# 08_MISC.net
KiCad netlist of a schematic drawn in Altium Designer
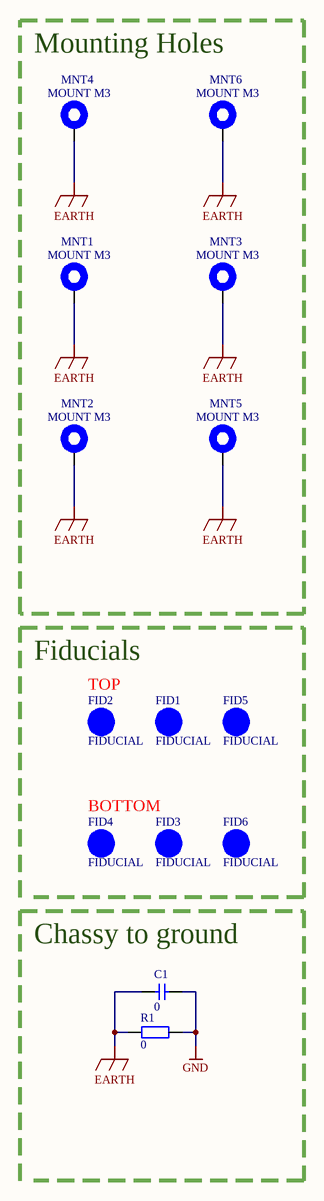
[diagram p0: 08 MISC.SchDoc]

(export (version "E")
  (design (tool "Eeschema 10.0.6"))
  (components
    (comp (ref "C1") (value "0") (footprint "CAPC2012X04N") (libsource (lib "altium_symbol") (part "TEMP_1")))
    (comp (ref "FID1")
      (value "FIDUCIAL")
      (footprint "FIDUCIAL")
      (libsource (lib "altium_symbol") (part "FIDUCIAL"))
    )
    (comp (ref "FID2")
      (value "FIDUCIAL")
      (footprint "FIDUCIAL")
      (libsource (lib "altium_symbol") (part "FIDUCIAL"))
    )
    (comp (ref "FID3")
      (value "FIDUCIAL")
      (footprint "FIDUCIAL")
      (libsource (lib "altium_symbol") (part "FIDUCIAL"))
    )
    (comp (ref "FID4")
      (value "FIDUCIAL")
      (footprint "FIDUCIAL")
      (libsource (lib "altium_symbol") (part "FIDUCIAL"))
    )
    (comp (ref "FID5")
      (value "FIDUCIAL")
      (footprint "FIDUCIAL")
      (libsource (lib "altium_symbol") (part "FIDUCIAL"))
    )
    (comp (ref "FID6")
      (value "FIDUCIAL")
      (footprint "FIDUCIAL")
      (libsource (lib "altium_symbol") (part "FIDUCIAL"))
    )
    (comp (ref "MNT1")
      (value "MOUNT M3")
      (footprint "MOUNT_M3")
      (libsource (lib "altium_symbol") (part "MOUNT_M3"))
    )
    (comp (ref "MNT2")
      (value "MOUNT M3")
      (footprint "MOUNT_M3")
      (libsource (lib "altium_symbol") (part "MOUNT_M3"))
    )
    (comp (ref "MNT3")
      (value "MOUNT M3")
      (footprint "MOUNT_M3")
      (libsource (lib "altium_symbol") (part "MOUNT_M3"))
    )
    (comp (ref "MNT4")
      (value "MOUNT M3")
      (footprint "MOUNT_M3")
      (libsource (lib "altium_symbol") (part "MOUNT_M3"))
    )
    (comp (ref "MNT5")
      (value "MOUNT M3")
      (footprint "MOUNT_M3")
      (libsource (lib "altium_symbol") (part "MOUNT_M3"))
    )
    (comp (ref "MNT6")
      (value "MOUNT M3")
      (footprint "MOUNT_M3")
      (libsource (lib "altium_symbol") (part "MOUNT_M3"))
    )
    (comp (ref "R1") (value "0") (footprint "RESC2012X04N") (libsource (lib "altium_symbol") (part "TEMP")))
  )
  (nets
    (net (code "1") (name "EARTH") (class "Default")
      (node (ref "C1") (pin "1") (pinfunction "1_1") (pintype "passive"))
      (node (ref "MNT1") (pin "1") (pinfunction "1_1") (pintype "passive"))
      (node (ref "MNT2") (pin "1") (pinfunction "1_1") (pintype "passive"))
      (node (ref "MNT3") (pin "1") (pinfunction "1_1") (pintype "passive"))
      (node (ref "MNT4") (pin "1") (pinfunction "1_1") (pintype "passive"))
      (node (ref "MNT5") (pin "1") (pinfunction "1_1") (pintype "passive"))
      (node (ref "MNT6") (pin "1") (pinfunction "1_1") (pintype "passive"))
      (node (ref "R1") (pin "1") (pinfunction "1_1") (pintype "passive"))
    )
    (net (code "2") (name "GND") (class "Default")
      (node (ref "C1") (pin "2") (pinfunction "2_2") (pintype "passive"))
      (node (ref "R1") (pin "2") (pinfunction "2_2") (pintype "passive"))
    )
  )
)
